# mainboard.net
KiCad netlist of a schematic drawn in EAGLE
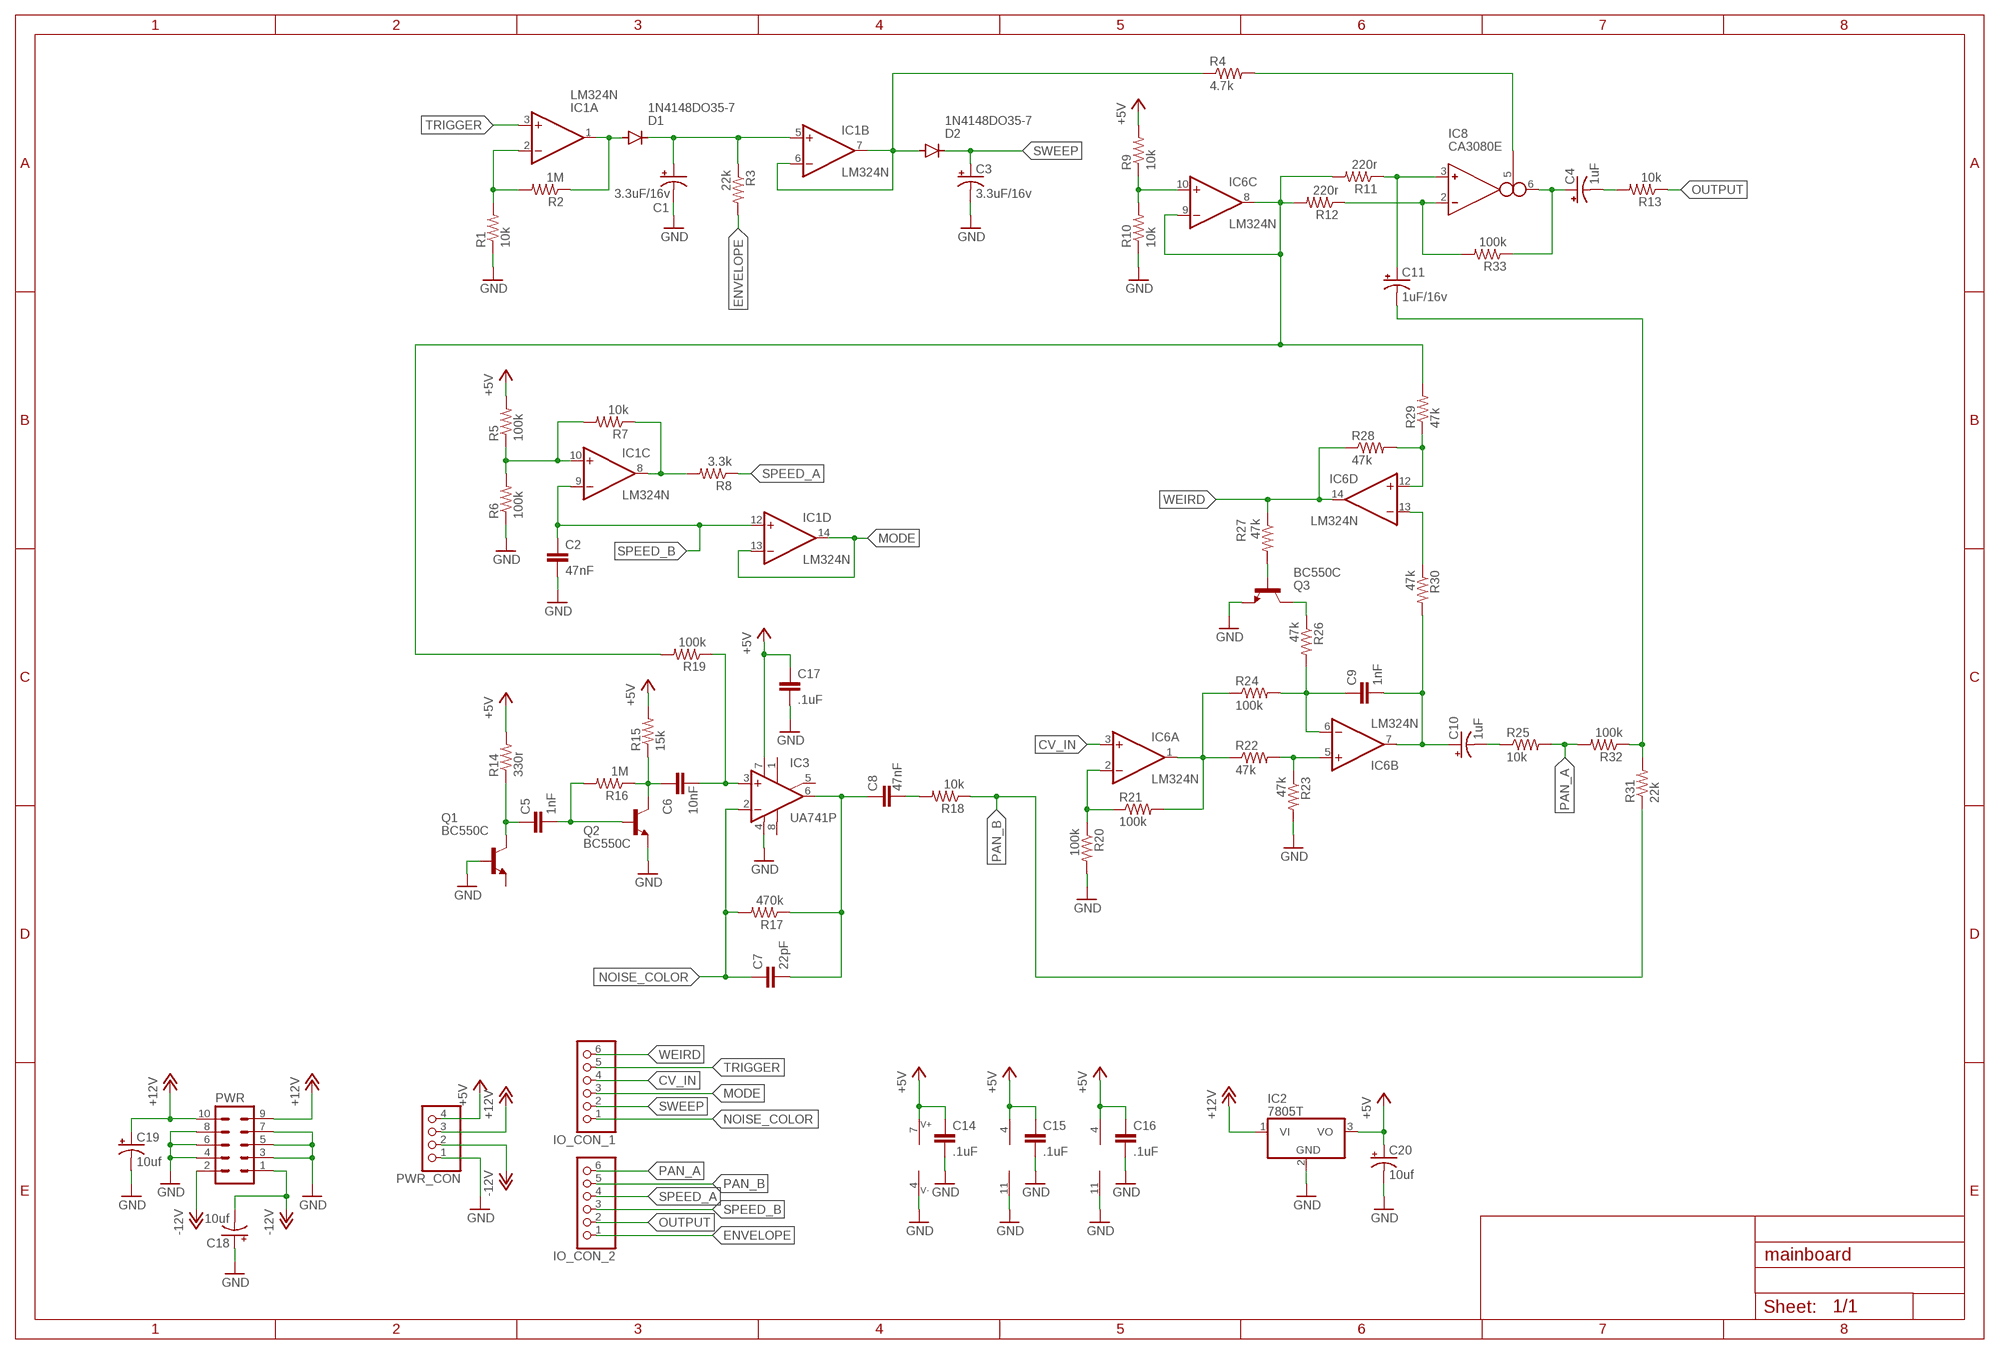
[diagram p0: schematic, sheet 1]

(export (version "E")
  (design (tool "Eeschema 10.0.6"))
  (components
    (comp (ref "C1")
      (value "3.3uF/16v")
      (footprint "eagle-import:E2,5-6")
      (libsource (lib "eagle-import") (part "CPOL-USE2.5-6"))
    )
    (comp (ref "C2")
      (value "47nF")
      (footprint "eagle-import:C050-024X044")
      (libsource (lib "eagle-import") (part "C-EU050-024X044"))
    )
    (comp (ref "C3")
      (value "3.3uF/16v")
      (footprint "eagle-import:E2,5-6")
      (libsource (lib "eagle-import") (part "CPOL-USE2.5-6"))
    )
    (comp (ref "C4")
      (value "1uF")
      (footprint "eagle-import:E2,5-6")
      (libsource (lib "eagle-import") (part "CPOL-USE2.5-6"))
    )
    (comp (ref "C5")
      (value "1nF")
      (footprint "eagle-import:C050-024X044")
      (libsource (lib "eagle-import") (part "C-EU050-024X044"))
    )
    (comp (ref "C6")
      (value "10nF")
      (footprint "eagle-import:C050-024X044")
      (libsource (lib "eagle-import") (part "C-EU050-024X044"))
    )
    (comp (ref "C7")
      (value "22pF")
      (footprint "eagle-import:C050-024X044")
      (libsource (lib "eagle-import") (part "C-EU050-024X044"))
    )
    (comp (ref "C8")
      (value "47nF")
      (footprint "eagle-import:C050-024X044")
      (libsource (lib "eagle-import") (part "C-EU050-024X044"))
    )
    (comp (ref "C9")
      (value "1nF")
      (footprint "eagle-import:C050-024X044")
      (libsource (lib "eagle-import") (part "C-EU050-024X044"))
    )
    (comp (ref "C10")
      (value "1uF")
      (footprint "eagle-import:E2,5-6")
      (libsource (lib "eagle-import") (part "CPOL-USE2.5-6"))
    )
    (comp (ref "C11")
      (value "1uF/16v")
      (footprint "eagle-import:E2,5-6")
      (libsource (lib "eagle-import") (part "CPOL-USE2.5-6"))
    )
    (comp (ref "C14")
      (value ".1uF")
      (footprint "eagle-import:C050-024X044")
      (libsource (lib "eagle-import") (part "C-EU050-024X044"))
    )
    (comp (ref "C15")
      (value ".1uF")
      (footprint "eagle-import:C050-024X044")
      (libsource (lib "eagle-import") (part "C-EU050-024X044"))
    )
    (comp (ref "C16")
      (value ".1uF")
      (footprint "eagle-import:C050-024X044")
      (libsource (lib "eagle-import") (part "C-EU050-024X044"))
    )
    (comp (ref "C17")
      (value ".1uF")
      (footprint "eagle-import:C050-024X044")
      (libsource (lib "eagle-import") (part "C-EU050-024X044"))
    )
    (comp (ref "C18")
      (value "10uf")
      (footprint "eagle-import:E2,5-5")
      (libsource (lib "eagle-import") (part "resistor_CPOL-USE2.5-5"))
    )
    (comp (ref "C19")
      (value "10uf")
      (footprint "eagle-import:E2,5-5")
      (libsource (lib "eagle-import") (part "resistor_CPOL-USE2.5-5"))
    )
    (comp (ref "C20")
      (value "10uf")
      (footprint "eagle-import:E2,5-5")
      (libsource (lib "eagle-import") (part "resistor_CPOL-USE2.5-5"))
    )
    (comp (ref "D1")
      (value "1N4148DO35-7")
      (footprint "eagle-import:DO35-7")
      (libsource (lib "eagle-import") (part "1N4148DO35-7"))
    )
    (comp (ref "D2")
      (value "1N4148DO35-7")
      (footprint "eagle-import:DO35-7")
      (libsource (lib "eagle-import") (part "1N4148DO35-7"))
    )
    (comp (ref "IC1")
      (value "LM324N")
      (footprint "eagle-import:DIL14")
      (libsource (lib "eagle-import") (part "LM324N"))
    )
    (comp (ref "IC2")
      (value "7805T")
      (footprint "eagle-import:TO220H")
      (libsource (lib "eagle-import") (part "78T05"))
    )
    (comp (ref "IC3")
      (value "UA741P")
      (footprint "eagle-import:DIL08")
      (libsource (lib "eagle-import") (part "741PUA"))
    )
    (comp (ref "IC6")
      (value "LM324N")
      (footprint "eagle-import:DIL14")
      (libsource (lib "eagle-import") (part "LM324N"))
    )
    (comp (ref "IC8")
      (value "CA3080E")
      (footprint "eagle-import:DIL08")
      (libsource (lib "eagle-import") (part "CA3080E"))
    )
    (comp (ref "IO_CON_1")
      (value "PINHD-1X6")
      (footprint "eagle-import:1X06")
      (libsource (lib "eagle-import") (part "PINHD-1X6"))
    )
    (comp (ref "IO_CON_2")
      (value "PINHD-1X6")
      (footprint "eagle-import:1X06")
      (libsource (lib "eagle-import") (part "PINHD-1X6"))
    )
    (comp (ref "PWR")
      (value "ML10")
      (footprint "eagle-import:ML10")
      (libsource (lib "eagle-import") (part "ML10"))
    )
    (comp (ref "PWR_CON")
      (value "PINHD-1X4")
      (footprint "eagle-import:1X04")
      (libsource (lib "eagle-import") (part "PINHD-1X4"))
    )
    (comp (ref "Q1")
      (value "BC550C")
      (footprint "eagle-import:TO92-EBC")
      (libsource (lib "eagle-import") (part "BC550C"))
    )
    (comp (ref "Q2")
      (value "BC550C")
      (footprint "eagle-import:TO92-EBC")
      (libsource (lib "eagle-import") (part "BC550C"))
    )
    (comp (ref "Q3")
      (value "BC550C")
      (footprint "eagle-import:TO92-EBC")
      (libsource (lib "eagle-import") (part "BC550C"))
    )
    (comp (ref "R1")
      (value "10k")
      (footprint "eagle-import:0207_7")
      (libsource (lib "eagle-import") (part "R-US_0207/7"))
    )
    (comp (ref "R2")
      (value "1M")
      (footprint "eagle-import:0207_7")
      (libsource (lib "eagle-import") (part "R-US_0207/7"))
    )
    (comp (ref "R3")
      (value "22k")
      (footprint "eagle-import:0207_7")
      (libsource (lib "eagle-import") (part "R-US_0207/7"))
    )
    (comp (ref "R4")
      (value "4.7k")
      (footprint "eagle-import:0207_7")
      (libsource (lib "eagle-import") (part "R-US_0207/7"))
    )
    (comp (ref "R5")
      (value "100k")
      (footprint "eagle-import:0207_7")
      (libsource (lib "eagle-import") (part "R-US_0207/7"))
    )
    (comp (ref "R6")
      (value "100k")
      (footprint "eagle-import:0207_7")
      (libsource (lib "eagle-import") (part "R-US_0207/7"))
    )
    (comp (ref "R7")
      (value "10k")
      (footprint "eagle-import:0207_7")
      (libsource (lib "eagle-import") (part "R-US_0207/7"))
    )
    (comp (ref "R8")
      (value "3.3k")
      (footprint "eagle-import:0207_7")
      (libsource (lib "eagle-import") (part "R-US_0207/7"))
    )
    (comp (ref "R9")
      (value "10k")
      (footprint "eagle-import:0207_7")
      (libsource (lib "eagle-import") (part "R-US_0207/7"))
    )
    (comp (ref "R10")
      (value "10k")
      (footprint "eagle-import:0207_7")
      (libsource (lib "eagle-import") (part "R-US_0207/7"))
    )
    (comp (ref "R11")
      (value "220r")
      (footprint "eagle-import:0207_7")
      (libsource (lib "eagle-import") (part "R-US_0207/7"))
    )
    (comp (ref "R12")
      (value "220r")
      (footprint "eagle-import:0207_7")
      (libsource (lib "eagle-import") (part "R-US_0207/7"))
    )
    (comp (ref "R13")
      (value "10k")
      (footprint "eagle-import:0207_7")
      (libsource (lib "eagle-import") (part "R-US_0207/7"))
    )
    (comp (ref "R14")
      (value "330r")
      (footprint "eagle-import:0207_7")
      (libsource (lib "eagle-import") (part "R-US_0207/7"))
    )
    (comp (ref "R15")
      (value "15k")
      (footprint "eagle-import:0207_7")
      (libsource (lib "eagle-import") (part "R-US_0207/7"))
    )
    (comp (ref "R16")
      (value "1M")
      (footprint "eagle-import:0207_7")
      (libsource (lib "eagle-import") (part "R-US_0207/7"))
    )
    (comp (ref "R17")
      (value "470k")
      (footprint "eagle-import:0207_7")
      (libsource (lib "eagle-import") (part "R-US_0207/7"))
    )
    (comp (ref "R18")
      (value "10k")
      (footprint "eagle-import:0207_7")
      (libsource (lib "eagle-import") (part "R-US_0207/7"))
    )
    (comp (ref "R19")
      (value "100k")
      (footprint "eagle-import:0207_7")
      (libsource (lib "eagle-import") (part "R-US_0207/7"))
    )
    (comp (ref "R20")
      (value "100k")
      (footprint "eagle-import:0207_7")
      (libsource (lib "eagle-import") (part "R-US_0207/7"))
    )
    (comp (ref "R21")
      (value "100k")
      (footprint "eagle-import:0207_7")
      (libsource (lib "eagle-import") (part "R-US_0207/7"))
    )
    (comp (ref "R22")
      (value "47k")
      (footprint "eagle-import:0207_7")
      (libsource (lib "eagle-import") (part "R-US_0207/7"))
    )
    (comp (ref "R23")
      (value "47k")
      (footprint "eagle-import:0207_7")
      (libsource (lib "eagle-import") (part "R-US_0207/7"))
    )
    (comp (ref "R24")
      (value "100k")
      (footprint "eagle-import:0207_7")
      (libsource (lib "eagle-import") (part "R-US_0207/7"))
    )
    (comp (ref "R25")
      (value "10k")
      (footprint "eagle-import:0207_7")
      (libsource (lib "eagle-import") (part "R-US_0207/7"))
    )
    (comp (ref "R26")
      (value "47k")
      (footprint "eagle-import:0207_7")
      (libsource (lib "eagle-import") (part "R-US_0207/7"))
    )
    (comp (ref "R27")
      (value "47k")
      (footprint "eagle-import:0207_7")
      (libsource (lib "eagle-import") (part "R-US_0207/7"))
    )
    (comp (ref "R28")
      (value "47k")
      (footprint "eagle-import:0207_7")
      (libsource (lib "eagle-import") (part "R-US_0207/7"))
    )
    (comp (ref "R29")
      (value "47k")
      (footprint "eagle-import:0207_7")
      (libsource (lib "eagle-import") (part "R-US_0207/7"))
    )
    (comp (ref "R30")
      (value "47k")
      (footprint "eagle-import:0207_7")
      (libsource (lib "eagle-import") (part "R-US_0207/7"))
    )
    (comp (ref "R31")
      (value "22k")
      (footprint "eagle-import:0207_7")
      (libsource (lib "eagle-import") (part "R-US_0207/7"))
    )
    (comp (ref "R32")
      (value "100k")
      (footprint "eagle-import:0207_7")
      (libsource (lib "eagle-import") (part "R-US_0207/7"))
    )
    (comp (ref "R33")
      (value "100k")
      (footprint "eagle-import:0207_7")
      (libsource (lib "eagle-import") (part "R-US_0207/7"))
    )
  )
  (nets
    (net (code "1") (name "+5V") (class "Default")
      (node (ref "C14") (pin "1") (pinfunction "1_1") (pintype "passive"))
      (node (ref "C15") (pin "1") (pinfunction "1_1") (pintype "passive"))
      (node (ref "C16") (pin "1") (pinfunction "1_1") (pintype "passive"))
      (node (ref "C17") (pin "1") (pinfunction "1_1") (pintype "passive"))
      (node (ref "C20") (pin "+") (pinfunction "+_+") (pintype "passive"))
      (node (ref "IC1") (pin "4") (pinfunction "V+_4") (pintype "power_in"))
      (node (ref "IC2") (pin "3") (pinfunction "VO_3") (pintype "passive"))
      (node (ref "IC3") (pin "7") (pinfunction "V+_7") (pintype "power_in"))
      (node (ref "IC6") (pin "4") (pinfunction "V+_4") (pintype "power_in"))
      (node (ref "IC8") (pin "7") (pinfunction "V+_7") (pintype "power_in"))
      (node (ref "PWR_CON") (pin "4") (pinfunction "4_4") (pintype "passive"))
      (node (ref "R14") (pin "2") (pinfunction "2_2") (pintype "passive"))
      (node (ref "R15") (pin "2") (pinfunction "2_2") (pintype "passive"))
      (node (ref "R5") (pin "2") (pinfunction "2_2") (pintype "passive"))
      (node (ref "R9") (pin "2") (pinfunction "2_2") (pintype "passive"))
    )
    (net (code "2") (name "+12V") (class "Default")
      (node (ref "C19") (pin "+") (pinfunction "+_+") (pintype "passive"))
      (node (ref "IC2") (pin "1") (pinfunction "VI_1") (pintype "input"))
      (node (ref "PWR") (pin "10") (pinfunction "10_10") (pintype "passive"))
      (node (ref "PWR") (pin "9") (pinfunction "9_9") (pintype "passive"))
      (node (ref "PWR_CON") (pin "3") (pinfunction "3_3") (pintype "passive"))
    )
    (net (code "3") (name "-12V") (class "Default")
      (node (ref "C18") (pin "-") (pinfunction "-_-") (pintype "passive"))
      (node (ref "PWR") (pin "1") (pinfunction "1_1") (pintype "passive"))
      (node (ref "PWR") (pin "2") (pinfunction "2_2") (pintype "passive"))
      (node (ref "PWR_CON") (pin "2") (pinfunction "2_2") (pintype "passive"))
    )
    (net (code "4") (name "CV_IN") (class "Default")
      (node (ref "IC6") (pin "3") (pinfunction "+IN_3") (pintype "input"))
      (node (ref "IO_CON_1") (pin "4") (pinfunction "4_4") (pintype "passive"))
    )
    (net (code "5") (name "ENVELOPE") (class "Default")
      (node (ref "IO_CON_2") (pin "1") (pinfunction "1_1") (pintype "passive"))
      (node (ref "R3") (pin "2") (pinfunction "2_2") (pintype "passive"))
    )
    (net (code "6") (name "GND") (class "Default")
      (node (ref "C1") (pin "-") (pinfunction "-_-") (pintype "passive"))
      (node (ref "C14") (pin "2") (pinfunction "2_2") (pintype "passive"))
      (node (ref "C15") (pin "2") (pinfunction "2_2") (pintype "passive"))
      (node (ref "C16") (pin "2") (pinfunction "2_2") (pintype "passive"))
      (node (ref "C17") (pin "2") (pinfunction "2_2") (pintype "passive"))
      (node (ref "C18") (pin "+") (pinfunction "+_+") (pintype "passive"))
      (node (ref "C19") (pin "-") (pinfunction "-_-") (pintype "passive"))
      (node (ref "C2") (pin "2") (pinfunction "2_2") (pintype "passive"))
      (node (ref "C20") (pin "-") (pinfunction "-_-") (pintype "passive"))
      (node (ref "C3") (pin "-") (pinfunction "-_-") (pintype "passive"))
      (node (ref "IC1") (pin "11") (pinfunction "V-_11") (pintype "power_in"))
      (node (ref "IC2") (pin "2") (pinfunction "GND_2") (pintype "passive"))
      (node (ref "IC3") (pin "4") (pinfunction "V-_4") (pintype "power_in"))
      (node (ref "IC6") (pin "11") (pinfunction "V-_11") (pintype "power_in"))
      (node (ref "IC8") (pin "4") (pinfunction "V-_4") (pintype "power_in"))
      (node (ref "PWR") (pin "3") (pinfunction "3_3") (pintype "passive"))
      (node (ref "PWR") (pin "4") (pinfunction "4_4") (pintype "passive"))
      (node (ref "PWR") (pin "5") (pinfunction "5_5") (pintype "passive"))
      (node (ref "PWR") (pin "6") (pinfunction "6_6") (pintype "passive"))
      (node (ref "PWR") (pin "7") (pinfunction "7_7") (pintype "passive"))
      (node (ref "PWR") (pin "8") (pinfunction "8_8") (pintype "passive"))
      (node (ref "PWR_CON") (pin "1") (pinfunction "1_1") (pintype "passive"))
      (node (ref "Q1") (pin "B") (pinfunction "B_B") (pintype "passive"))
      (node (ref "Q2") (pin "E") (pinfunction "E_E") (pintype "passive"))
      (node (ref "Q3") (pin "E") (pinfunction "E_E") (pintype "passive"))
      (node (ref "R1") (pin "1") (pinfunction "1_1") (pintype "passive"))
      (node (ref "R10") (pin "1") (pinfunction "1_1") (pintype "passive"))
      (node (ref "R20") (pin "2") (pinfunction "2_2") (pintype "passive"))
      (node (ref "R23") (pin "2") (pinfunction "2_2") (pintype "passive"))
      (node (ref "R6") (pin "1") (pinfunction "1_1") (pintype "passive"))
    )
    (net (code "7") (name "MODE") (class "Default")
      (node (ref "IC1") (pin "13") (pinfunction "-IN_13") (pintype "input"))
      (node (ref "IC1") (pin "14") (pinfunction "OUT_14") (pintype "output"))
      (node (ref "IO_CON_1") (pin "3") (pinfunction "3_3") (pintype "passive"))
    )
    (net (code "8") (name "NOISE_COLOR") (class "Default")
      (node (ref "C7") (pin "1") (pinfunction "1_1") (pintype "passive"))
      (node (ref "IC3") (pin "2") (pinfunction "-IN_2") (pintype "input"))
      (node (ref "IO_CON_1") (pin "1") (pinfunction "1_1") (pintype "passive"))
      (node (ref "R17") (pin "2") (pinfunction "2_2") (pintype "passive"))
    )
    (net (code "9") (name "Net-(C4-Pad-)") (class "Default")
      (node (ref "C4") (pin "-") (pinfunction "-_-") (pintype "passive"))
      (node (ref "R13") (pin "2") (pinfunction "2_2") (pintype "passive"))
    )
    (net (code "10") (name "Net-(C5-Pad1)") (class "Default")
      (node (ref "C5") (pin "1") (pinfunction "1_1") (pintype "passive"))
      (node (ref "Q1") (pin "C") (pinfunction "C_C") (pintype "passive"))
      (node (ref "R14") (pin "1") (pinfunction "1_1") (pintype "passive"))
    )
    (net (code "11") (name "Net-(C5-Pad2)") (class "Default")
      (node (ref "C5") (pin "2") (pinfunction "2_2") (pintype "passive"))
      (node (ref "Q2") (pin "B") (pinfunction "B_B") (pintype "passive"))
      (node (ref "R16") (pin "2") (pinfunction "2_2") (pintype "passive"))
    )
    (net (code "12") (name "Net-(C6-Pad1)") (class "Default")
      (node (ref "C6") (pin "1") (pinfunction "1_1") (pintype "passive"))
      (node (ref "Q2") (pin "C") (pinfunction "C_C") (pintype "passive"))
      (node (ref "R15") (pin "1") (pinfunction "1_1") (pintype "passive"))
      (node (ref "R16") (pin "1") (pinfunction "1_1") (pintype "passive"))
    )
    (net (code "13") (name "Net-(C8-Pad2)") (class "Default")
      (node (ref "C8") (pin "2") (pinfunction "2_2") (pintype "passive"))
      (node (ref "R18") (pin "2") (pinfunction "2_2") (pintype "passive"))
    )
    (net (code "14") (name "Net-(C10-Pad-)") (class "Default")
      (node (ref "C10") (pin "-") (pinfunction "-_-") (pintype "passive"))
      (node (ref "R25") (pin "1") (pinfunction "1_1") (pintype "passive"))
    )
    (net (code "15") (name "Net-(C11-Pad-)") (class "Default")
      (node (ref "C11") (pin "-") (pinfunction "-_-") (pintype "passive"))
      (node (ref "R31") (pin "2") (pinfunction "2_2") (pintype "passive"))
      (node (ref "R32") (pin "1") (pinfunction "1_1") (pintype "passive"))
    )
    (net (code "16") (name "Net-(IC1A--IN)") (class "Default")
      (node (ref "IC1") (pin "2") (pinfunction "-IN_2") (pintype "input"))
      (node (ref "R1") (pin "2") (pinfunction "2_2") (pintype "passive"))
      (node (ref "R2") (pin "2") (pinfunction "2_2") (pintype "passive"))
    )
    (net (code "17") (name "Net-(IC1A-OUT)") (class "Default")
      (node (ref "D1") (pin "A") (pinfunction "A_A") (pintype "passive"))
      (node (ref "IC1") (pin "1") (pinfunction "OUT_1") (pintype "output"))
      (node (ref "R2") (pin "1") (pinfunction "1_1") (pintype "passive"))
    )
    (net (code "18") (name "Net-(IC1B-+IN)") (class "Default")
      (node (ref "C1") (pin "+") (pinfunction "+_+") (pintype "passive"))
      (node (ref "D1") (pin "C") (pinfunction "C_C") (pintype "passive"))
      (node (ref "IC1") (pin "5") (pinfunction "+IN_5") (pintype "input"))
      (node (ref "R3") (pin "1") (pinfunction "1_1") (pintype "passive"))
    )
    (net (code "19") (name "Net-(IC1B--IN)") (class "Default")
      (node (ref "D2") (pin "A") (pinfunction "A_A") (pintype "passive"))
      (node (ref "IC1") (pin "6") (pinfunction "-IN_6") (pintype "input"))
      (node (ref "IC1") (pin "7") (pinfunction "OUT_7") (pintype "output"))
      (node (ref "R4") (pin "1") (pinfunction "1_1") (pintype "passive"))
    )
    (net (code "20") (name "Net-(IC1C-+IN)") (class "Default")
      (node (ref "IC1") (pin "10") (pinfunction "+IN_10") (pintype "input"))
      (node (ref "R5") (pin "1") (pinfunction "1_1") (pintype "passive"))
      (node (ref "R6") (pin "2") (pinfunction "2_2") (pintype "passive"))
      (node (ref "R7") (pin "2") (pinfunction "2_2") (pintype "passive"))
    )
    (net (code "21") (name "Net-(IC1C-OUT)") (class "Default")
      (node (ref "IC1") (pin "8") (pinfunction "OUT_8") (pintype "output"))
      (node (ref "R7") (pin "1") (pinfunction "1_1") (pintype "passive"))
      (node (ref "R8") (pin "2") (pinfunction "2_2") (pintype "passive"))
    )
    (net (code "22") (name "Net-(IC3-+IN)") (class "Default")
      (node (ref "C6") (pin "2") (pinfunction "2_2") (pintype "passive"))
      (node (ref "IC3") (pin "3") (pinfunction "+IN_3") (pintype "input"))
      (node (ref "R19") (pin "1") (pinfunction "1_1") (pintype "passive"))
    )
    (net (code "23") (name "Net-(IC3-OUT)") (class "Default")
      (node (ref "C7") (pin "2") (pinfunction "2_2") (pintype "passive"))
      (node (ref "C8") (pin "1") (pinfunction "1_1") (pintype "passive"))
      (node (ref "IC3") (pin "6") (pinfunction "OUT_6") (pintype "output"))
      (node (ref "R17") (pin "1") (pinfunction "1_1") (pintype "passive"))
    )
    (net (code "24") (name "Net-(IC6A--IN)") (class "Default")
      (node (ref "IC6") (pin "2") (pinfunction "-IN_2") (pintype "input"))
      (node (ref "R20") (pin "1") (pinfunction "1_1") (pintype "passive"))
      (node (ref "R21") (pin "1") (pinfunction "1_1") (pintype "passive"))
    )
    (net (code "25") (name "Net-(IC6A-OUT)") (class "Default")
      (node (ref "IC6") (pin "1") (pinfunction "OUT_1") (pintype "output"))
      (node (ref "R21") (pin "2") (pinfunction "2_2") (pintype "passive"))
      (node (ref "R22") (pin "1") (pinfunction "1_1") (pintype "passive"))
      (node (ref "R24") (pin "1") (pinfunction "1_1") (pintype "passive"))
    )
    (net (code "26") (name "Net-(IC6B-+IN)") (class "Default")
      (node (ref "IC6") (pin "5") (pinfunction "+IN_5") (pintype "input"))
      (node (ref "R22") (pin "2") (pinfunction "2_2") (pintype "passive"))
      (node (ref "R23") (pin "1") (pinfunction "1_1") (pintype "passive"))
    )
    (net (code "27") (name "Net-(IC6B--IN)") (class "Default")
      (node (ref "C9") (pin "1") (pinfunction "1_1") (pintype "passive"))
      (node (ref "IC6") (pin "6") (pinfunction "-IN_6") (pintype "input"))
      (node (ref "R24") (pin "2") (pinfunction "2_2") (pintype "passive"))
      (node (ref "R26") (pin "2") (pinfunction "2_2") (pintype "passive"))
    )
    (net (code "28") (name "Net-(IC6B-OUT)") (class "Default")
      (node (ref "C10") (pin "+") (pinfunction "+_+") (pintype "passive"))
      (node (ref "C9") (pin "2") (pinfunction "2_2") (pintype "passive"))
      (node (ref "IC6") (pin "7") (pinfunction "OUT_7") (pintype "output"))
      (node (ref "R30") (pin "2") (pinfunction "2_2") (pintype "passive"))
    )
    (net (code "29") (name "Net-(IC6C-+IN)") (class "Default")
      (node (ref "IC6") (pin "10") (pinfunction "+IN_10") (pintype "input"))
      (node (ref "R10") (pin "2") (pinfunction "2_2") (pintype "passive"))
      (node (ref "R9") (pin "1") (pinfunction "1_1") (pintype "passive"))
    )
    (net (code "30") (name "Net-(IC6C--IN)") (class "Default")
      (node (ref "IC6") (pin "8") (pinfunction "OUT_8") (pintype "output"))
      (node (ref "IC6") (pin "9") (pinfunction "-IN_9") (pintype "input"))
      (node (ref "R11") (pin "2") (pinfunction "2_2") (pintype "passive"))
      (node (ref "R12") (pin "2") (pinfunction "2_2") (pintype "passive"))
      (node (ref "R19") (pin "2") (pinfunction "2_2") (pintype "passive"))
      (node (ref "R29") (pin "2") (pinfunction "2_2") (pintype "passive"))
    )
    (net (code "31") (name "Net-(IC6D-+IN)") (class "Default")
      (node (ref "IC6") (pin "12") (pinfunction "+IN_12") (pintype "input"))
      (node (ref "R28") (pin "2") (pinfunction "2_2") (pintype "passive"))
      (node (ref "R29") (pin "1") (pinfunction "1_1") (pintype "passive"))
    )
    (net (code "32") (name "Net-(IC6D--IN)") (class "Default")
      (node (ref "IC6") (pin "13") (pinfunction "-IN_13") (pintype "input"))
      (node (ref "R30") (pin "1") (pinfunction "1_1") (pintype "passive"))
    )
    (net (code "33") (name "Net-(IC8A-IN_N)") (class "Default")
      (node (ref "IC8") (pin "2") (pinfunction "IN_N_2") (pintype "input"))
      (node (ref "R12") (pin "1") (pinfunction "1_1") (pintype "passive"))
      (node (ref "R33") (pin "2") (pinfunction "2_2") (pintype "passive"))
    )
    (net (code "34") (name "Net-(IC8A-IN_P)") (class "Default")
      (node (ref "C11") (pin "+") (pinfunction "+_+") (pintype "passive"))
      (node (ref "IC8") (pin "3") (pinfunction "IN_P_3") (pintype "input"))
      (node (ref "R11") (pin "1") (pinfunction "1_1") (pintype "passive"))
    )
    (net (code "35") (name "Net-(IC8A-I_BIAS)") (class "Default")
      (node (ref "IC8") (pin "5") (pinfunction "I_BIAS_5") (pintype "input"))
      (node (ref "R4") (pin "2") (pinfunction "2_2") (pintype "passive"))
    )
    (net (code "36") (name "Net-(IC8A-OUT)") (class "Default")
      (node (ref "C4") (pin "+") (pinfunction "+_+") (pintype "passive"))
      (node (ref "IC8") (pin "6") (pinfunction "OUT_6") (pintype "output"))
      (node (ref "R33") (pin "1") (pinfunction "1_1") (pintype "passive"))
    )
    (net (code "37") (name "Net-(Q3-PadB)") (class "Default")
      (node (ref "Q3") (pin "B") (pinfunction "B_B") (pintype "passive"))
      (node (ref "R27") (pin "2") (pinfunction "2_2") (pintype "passive"))
    )
    (net (code "38") (name "Net-(Q3-PadC)") (class "Default")
      (node (ref "Q3") (pin "C") (pinfunction "C_C") (pintype "passive"))
      (node (ref "R26") (pin "1") (pinfunction "1_1") (pintype "passive"))
    )
    (net (code "39") (name "OUTPUT") (class "Default")
      (node (ref "IO_CON_2") (pin "2") (pinfunction "2_2") (pintype "passive"))
      (node (ref "R13") (pin "1") (pinfunction "1_1") (pintype "passive"))
    )
    (net (code "40") (name "PAN_A") (class "Default")
      (node (ref "IO_CON_2") (pin "6") (pinfunction "6_6") (pintype "passive"))
      (node (ref "R25") (pin "2") (pinfunction "2_2") (pintype "passive"))
      (node (ref "R32") (pin "2") (pinfunction "2_2") (pintype "passive"))
    )
    (net (code "41") (name "PAN_B") (class "Default")
      (node (ref "IO_CON_2") (pin "5") (pinfunction "5_5") (pintype "passive"))
      (node (ref "R18") (pin "1") (pinfunction "1_1") (pintype "passive"))
      (node (ref "R31") (pin "1") (pinfunction "1_1") (pintype "passive"))
    )
    (net (code "42") (name "SPEED_A") (class "Default")
      (node (ref "IO_CON_2") (pin "4") (pinfunction "4_4") (pintype "passive"))
      (node (ref "R8") (pin "1") (pinfunction "1_1") (pintype "passive"))
    )
    (net (code "43") (name "SPEED_B") (class "Default")
      (node (ref "C2") (pin "1") (pinfunction "1_1") (pintype "passive"))
      (node (ref "IC1") (pin "12") (pinfunction "+IN_12") (pintype "input"))
      (node (ref "IC1") (pin "9") (pinfunction "-IN_9") (pintype "input"))
      (node (ref "IO_CON_2") (pin "3") (pinfunction "3_3") (pintype "passive"))
    )
    (net (code "44") (name "SWEEP") (class "Default")
      (node (ref "C3") (pin "+") (pinfunction "+_+") (pintype "passive"))
      (node (ref "D2") (pin "C") (pinfunction "C_C") (pintype "passive"))
      (node (ref "IO_CON_1") (pin "2") (pinfunction "2_2") (pintype "passive"))
    )
    (net (code "45") (name "TRIGGER") (class "Default")
      (node (ref "IC1") (pin "3") (pinfunction "+IN_3") (pintype "input"))
      (node (ref "IO_CON_1") (pin "5") (pinfunction "5_5") (pintype "passive"))
    )
    (net (code "46") (name "WEIRD") (class "Default")
      (node (ref "IC6") (pin "14") (pinfunction "OUT_14") (pintype "output"))
      (node (ref "IO_CON_1") (pin "6") (pinfunction "6_6") (pintype "passive"))
      (node (ref "R27") (pin "1") (pinfunction "1_1") (pintype "passive"))
      (node (ref "R28") (pin "1") (pinfunction "1_1") (pintype "passive"))
    )
    (net (code "47") (name "unconnected-(IC3-ON1-Pad1)") (class "Default")
      (node (ref "IC3") (pin "1") (pinfunction "ON1_1") (pintype "passive"))
    )
    (net (code "48") (name "unconnected-(IC3-ON2-Pad5)") (class "Default")
      (node (ref "IC3") (pin "5") (pinfunction "ON2_5") (pintype "passive"))
    )
    (net (code "49") (name "unconnected-(IC3-OPT-Pad8)") (class "Default")
      (node (ref "IC3") (pin "8") (pinfunction "OPT_8") (pintype "passive"))
    )
    (net (code "50") (name "unconnected-(Q1-PadE)") (class "Default")
      (node (ref "Q1") (pin "E") (pinfunction "E_E") (pintype "passive"))
    )
  )
)
